# sensor_expansion.net
KiCad netlist of a schematic drawn in Altium Designer
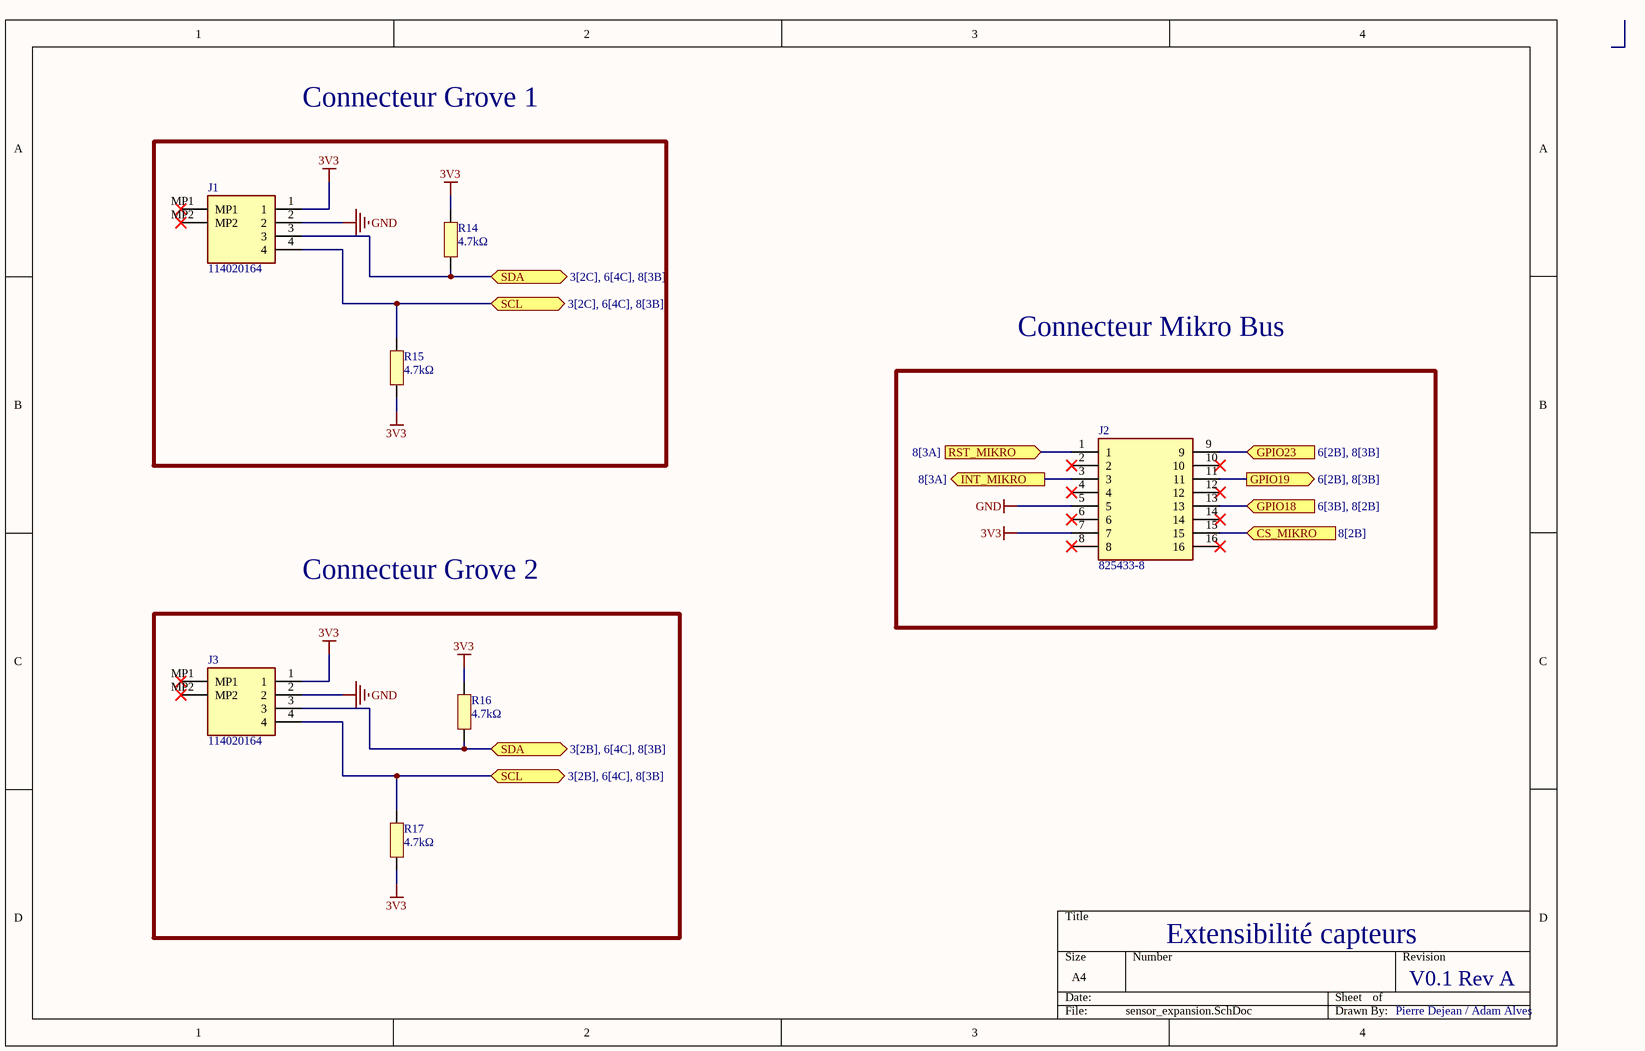
[diagram p0: sensor_expansion.SchDoc]

(export (version "E")
  (design (tool "Eeschema 10.0.6"))
  (components
    (comp (ref "J1")
      (value "114020164")
      (footprint "114020164")
      (description "Seeed Studio Accessories Grove Female Header - SMD-4P-2.0mm-90D-20Pcs")
      (fields (field (name "MOUSER PART NUMBER") "713-114020164"))
      (libsource (lib "SCHLibrary") (part "114020164"))
    )
    (comp (ref "J2")
      (value "825433-8")
      (footprint "Connect-Mikrobus")
      (description "Headers & Wire Housings 8P double for connection mikrobus")
      (fields (field (name "MOUSER PART NUMBER") "571-825433-8"))
      (libsource (lib "SCHLibrary") (part "Connect-Mikrobus"))
    )
    (comp (ref "J3")
      (value "114020164")
      (footprint "114020164")
      (description "Seeed Studio Accessories Grove Female Header - SMD-4P-2.0mm-90D-20Pcs")
      (fields (field (name "MOUSER PART NUMBER") "713-114020164"))
      (libsource (lib "SCHLibrary") (part "114020164"))
    )
    (comp (ref "R14") (value "4.7kΩ") (footprint "RESC1005X06N") (libsource (lib "") (part "Resistor_1")))
    (comp (ref "R15")
      (value "4.7kΩ")
      (footprint "RESC1005X06N")
      (libsource (lib "SCHLibrary") (part "Resistor"))
    )
    (comp (ref "R16") (value "4.7kΩ") (footprint "RESC1005X06N") (libsource (lib "") (part "Resistor_1")))
    (comp (ref "R17")
      (value "4.7kΩ")
      (footprint "RESC1005X06N")
      (libsource (lib "SCHLibrary") (part "Resistor"))
    )
  )
  (nets
    (net (code "1") (name "/CS_MIKRO") (class "Default")
      (node (ref "J2") (pin "15") (pinfunction "15_15") (pintype "passive"))
    )
    (net (code "2") (name "/GPIO18") (class "Default")
      (node (ref "J2") (pin "13") (pinfunction "13_13") (pintype "passive"))
    )
    (net (code "3") (name "/GPIO19") (class "Default")
      (node (ref "J2") (pin "11") (pinfunction "11_11") (pintype "passive"))
    )
    (net (code "4") (name "/GPIO23") (class "Default")
      (node (ref "J2") (pin "9") (pinfunction "9_9") (pintype "passive"))
    )
    (net (code "5") (name "/INT_MIKRO") (class "Default")
      (node (ref "J2") (pin "3") (pinfunction "3_3") (pintype "passive"))
    )
    (net (code "6") (name "/RST_MIKRO") (class "Default")
      (node (ref "J2") (pin "1") (pinfunction "1_1") (pintype "passive"))
    )
    (net (code "7") (name "/SCL") (class "Default")
      (node (ref "J1") (pin "4") (pinfunction "4_4") (pintype "passive"))
      (node (ref "J3") (pin "4") (pinfunction "4_4") (pintype "passive"))
      (node (ref "R15") (pin "2") (pinfunction "2_2") (pintype "passive"))
      (node (ref "R17") (pin "2") (pinfunction "2_2") (pintype "passive"))
    )
    (net (code "8") (name "/SDA") (class "Default")
      (node (ref "J1") (pin "3") (pinfunction "3_3") (pintype "passive"))
      (node (ref "J3") (pin "3") (pinfunction "3_3") (pintype "passive"))
      (node (ref "R14") (pin "2") (pinfunction "2_2") (pintype "passive"))
      (node (ref "R16") (pin "2") (pinfunction "2_2") (pintype "passive"))
    )
    (net (code "9") (name "3V3") (class "Default")
      (node (ref "J1") (pin "1") (pinfunction "1_1") (pintype "passive"))
      (node (ref "J2") (pin "7") (pinfunction "7_7") (pintype "passive"))
      (node (ref "J3") (pin "1") (pinfunction "1_1") (pintype "passive"))
      (node (ref "R14") (pin "1") (pinfunction "1_1") (pintype "passive"))
      (node (ref "R15") (pin "1") (pinfunction "1_1") (pintype "passive"))
      (node (ref "R16") (pin "1") (pinfunction "1_1") (pintype "passive"))
      (node (ref "R17") (pin "1") (pinfunction "1_1") (pintype "passive"))
    )
    (net (code "10") (name "GND") (class "Default")
      (node (ref "J1") (pin "2") (pinfunction "2_2") (pintype "passive"))
      (node (ref "J2") (pin "5") (pinfunction "5_5") (pintype "passive"))
      (node (ref "J3") (pin "2") (pinfunction "2_2") (pintype "passive"))
    )
    (net (code "11") (name "unconnected-(J1-PadMP1)") (class "Default")
      (node (ref "J1") (pin "MP1") (pinfunction "MP1_MP1") (pintype "passive+no_connect"))
    )
    (net (code "12") (name "unconnected-(J1-PadMP2)") (class "Default")
      (node (ref "J1") (pin "MP2") (pinfunction "MP2_MP2") (pintype "passive+no_connect"))
    )
    (net (code "13") (name "unconnected-(J2-Pad2)") (class "Default")
      (node (ref "J2") (pin "2") (pinfunction "2_2") (pintype "passive+no_connect"))
    )
    (net (code "14") (name "unconnected-(J2-Pad4)") (class "Default")
      (node (ref "J2") (pin "4") (pinfunction "4_4") (pintype "passive+no_connect"))
    )
    (net (code "15") (name "unconnected-(J2-Pad6)") (class "Default")
      (node (ref "J2") (pin "6") (pinfunction "6_6") (pintype "passive+no_connect"))
    )
    (net (code "16") (name "unconnected-(J2-Pad8)") (class "Default")
      (node (ref "J2") (pin "8") (pinfunction "8_8") (pintype "passive+no_connect"))
    )
    (net (code "17") (name "unconnected-(J2-Pad10)") (class "Default")
      (node (ref "J2") (pin "10") (pinfunction "10_10") (pintype "passive+no_connect"))
    )
    (net (code "18") (name "unconnected-(J2-Pad12)") (class "Default")
      (node (ref "J2") (pin "12") (pinfunction "12_12") (pintype "passive+no_connect"))
    )
    (net (code "19") (name "unconnected-(J2-Pad14)") (class "Default")
      (node (ref "J2") (pin "14") (pinfunction "14_14") (pintype "passive+no_connect"))
    )
    (net (code "20") (name "unconnected-(J2-Pad16)") (class "Default")
      (node (ref "J2") (pin "16") (pinfunction "16_16") (pintype "passive+no_connect"))
    )
    (net (code "21") (name "unconnected-(J3-PadMP1)") (class "Default")
      (node (ref "J3") (pin "MP1") (pinfunction "MP1_MP1") (pintype "passive+no_connect"))
    )
    (net (code "22") (name "unconnected-(J3-PadMP2)") (class "Default")
      (node (ref "J3") (pin "MP2") (pinfunction "MP2_MP2") (pintype "passive+no_connect"))
    )
  )
)
